# leo_FLOORSEN.net
KiCad netlist of a schematic drawn in Altium Designer
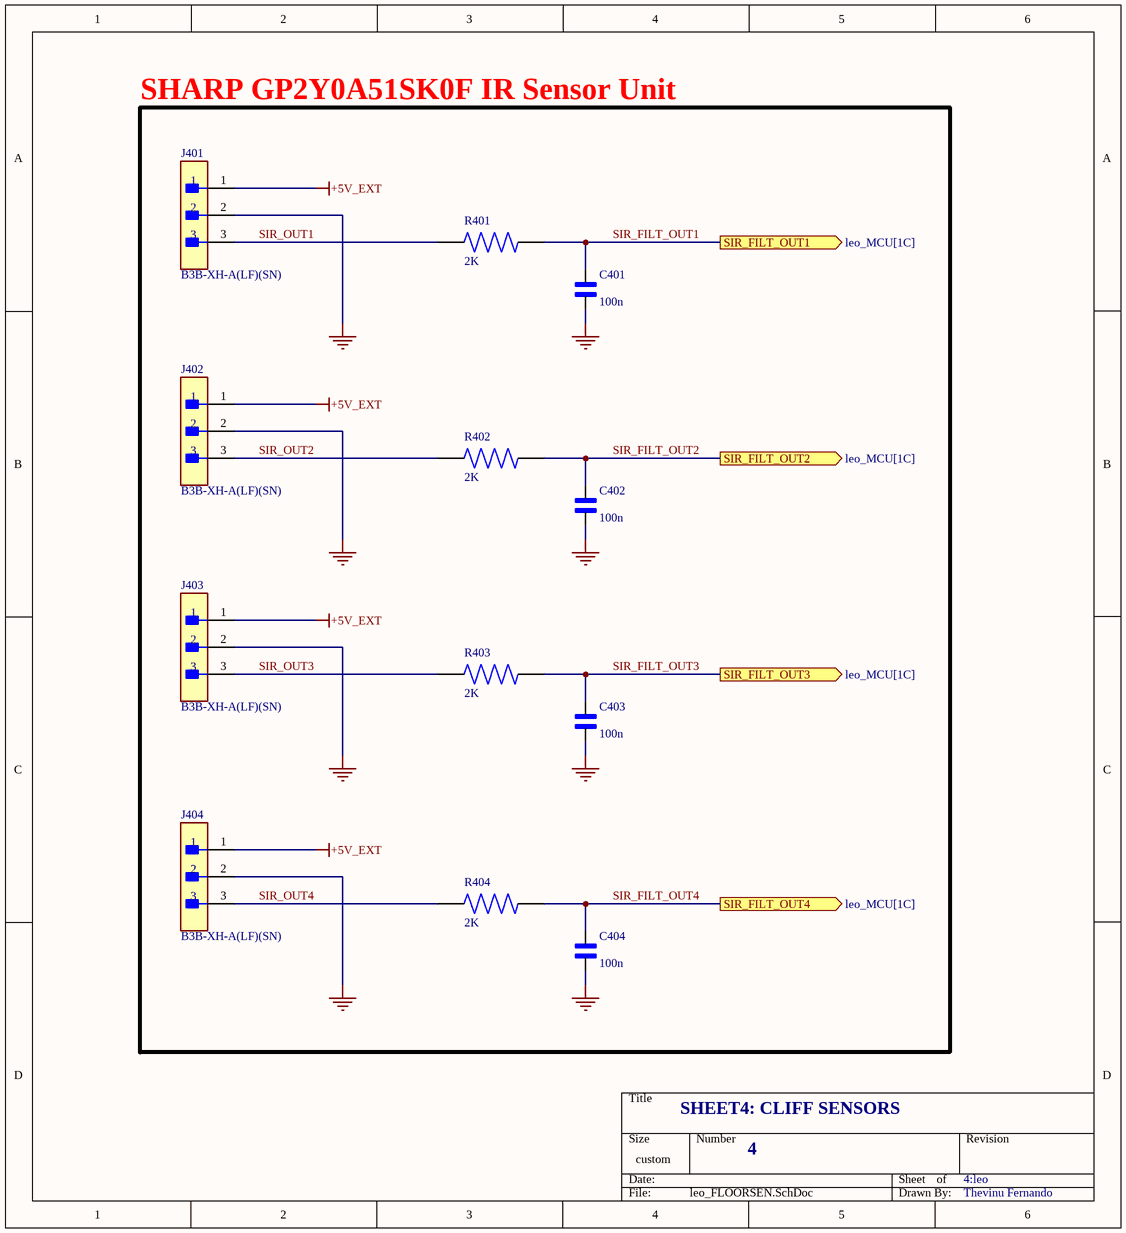
[diagram p0: leo_FLOORSEN.SchDoc]

(export (version "E")
  (design (tool "Eeschema 10.0.6"))
  (components
    (comp (ref "C401")
      (value "100n")
      (footprint "CAP_0402")
      (description "Ceramic Capacitor X7R 0402 (1005 Metric)")
      (fields (field (name "MF") "Samsung") (field (name "MP") "CL05B104KO5NNNC"))
      (libsource (lib "leo_schlib") (part "CAP_0402"))
    )
    (comp (ref "C402")
      (value "100n")
      (footprint "CAP_0402")
      (description "Ceramic Capacitor X7R 0402 (1005 Metric)")
      (fields (field (name "MF") "Samsung") (field (name "MP") "CL05B104KO5NNNC"))
      (libsource (lib "leo_schlib") (part "CAP_0402"))
    )
    (comp (ref "C403")
      (value "100n")
      (footprint "CAP_0402")
      (description "Ceramic Capacitor X7R 0402 (1005 Metric)")
      (fields (field (name "MF") "Samsung") (field (name "MP") "CL05B104KO5NNNC"))
      (libsource (lib "leo_schlib") (part "CAP_0402"))
    )
    (comp (ref "C404")
      (value "100n")
      (footprint "CAP_0402")
      (description "Ceramic Capacitor X7R 0402 (1005 Metric)")
      (fields (field (name "MF") "Samsung") (field (name "MP") "CL05B104KO5NNNC"))
      (libsource (lib "leo_schlib") (part "CAP_0402"))
    )
    (comp (ref "J401")
      (value "B3B-XH-A(LF)(SN)")
      (footprint "FP-B3B-XH-A_LF_SN-MFG")
      (description "CONN HEADER VERT 3POS 2.5MM")
      (libsource (lib "leo_schlib") (part "B3B-XH-A(LF)(SN)"))
    )
    (comp (ref "J402")
      (value "B3B-XH-A(LF)(SN)")
      (footprint "FP-B3B-XH-A_LF_SN-MFG")
      (description "CONN HEADER VERT 3POS 2.5MM")
      (libsource (lib "leo_schlib") (part "B3B-XH-A(LF)(SN)"))
    )
    (comp (ref "J403")
      (value "B3B-XH-A(LF)(SN)")
      (footprint "FP-B3B-XH-A_LF_SN-MFG")
      (description "CONN HEADER VERT 3POS 2.5MM")
      (libsource (lib "leo_schlib") (part "B3B-XH-A(LF)(SN)"))
    )
    (comp (ref "J404")
      (value "B3B-XH-A(LF)(SN)")
      (footprint "FP-B3B-XH-A_LF_SN-MFG")
      (description "CONN HEADER VERT 3POS 2.5MM")
      (libsource (lib "leo_schlib") (part "B3B-XH-A(LF)(SN)"))
    )
    (comp (ref "R401")
      (value "2K")
      (footprint "RES_0402")
      (description "Chip Resistor 0402 (1005 Metric) Automotive AEC-Q200 Thick Film")
      (fields (field (name "MF") "Panasonic") (field (name "MP") "ERJ-2RKF1002X"))
      (libsource (lib "leo_schlib") (part "RES_0402"))
    )
    (comp (ref "R402")
      (value "2K")
      (footprint "RES_0402")
      (description "Chip Resistor 0402 (1005 Metric) Automotive AEC-Q200 Thick Film")
      (fields (field (name "MF") "Panasonic") (field (name "MP") "ERJ-2RKF1002X"))
      (libsource (lib "leo_schlib") (part "RES_0402"))
    )
    (comp (ref "R403")
      (value "2K")
      (footprint "RES_0402")
      (description "Chip Resistor 0402 (1005 Metric) Automotive AEC-Q200 Thick Film")
      (fields (field (name "MF") "Panasonic") (field (name "MP") "ERJ-2RKF1002X"))
      (libsource (lib "leo_schlib") (part "RES_0402"))
    )
    (comp (ref "R404")
      (value "2K")
      (footprint "RES_0402")
      (description "Chip Resistor 0402 (1005 Metric) Automotive AEC-Q200 Thick Film")
      (fields (field (name "MF") "Panasonic") (field (name "MP") "ERJ-2RKF1002X"))
      (libsource (lib "leo_schlib") (part "RES_0402"))
    )
  )
  (nets
    (net (code "1") (name "+5V_EXT") (class "Default")
      (node (ref "J401") (pin "1") (pinfunction "1_1") (pintype "passive"))
      (node (ref "J402") (pin "1") (pinfunction "1_1") (pintype "passive"))
      (node (ref "J403") (pin "1") (pinfunction "1_1") (pintype "passive"))
      (node (ref "J404") (pin "1") (pinfunction "1_1") (pintype "passive"))
    )
    (net (code "2") (name "/SIR_FILT_OUT1") (class "Default")
      (node (ref "C401") (pin "2") (pinfunction "2_2") (pintype "passive"))
      (node (ref "R401") (pin "2") (pinfunction "2_2") (pintype "passive"))
    )
    (net (code "3") (name "/SIR_FILT_OUT2") (class "Default")
      (node (ref "C402") (pin "2") (pinfunction "2_2") (pintype "passive"))
      (node (ref "R402") (pin "2") (pinfunction "2_2") (pintype "passive"))
    )
    (net (code "4") (name "/SIR_FILT_OUT3") (class "Default")
      (node (ref "C403") (pin "2") (pinfunction "2_2") (pintype "passive"))
      (node (ref "R403") (pin "2") (pinfunction "2_2") (pintype "passive"))
    )
    (net (code "5") (name "/SIR_FILT_OUT4") (class "Default")
      (node (ref "C404") (pin "2") (pinfunction "2_2") (pintype "passive"))
      (node (ref "R404") (pin "2") (pinfunction "2_2") (pintype "passive"))
    )
    (net (code "6") (name "/SIR_OUT1") (class "Default")
      (node (ref "J401") (pin "3") (pinfunction "3_3") (pintype "passive"))
      (node (ref "R401") (pin "1") (pinfunction "1_1") (pintype "passive"))
    )
    (net (code "7") (name "/SIR_OUT2") (class "Default")
      (node (ref "J402") (pin "3") (pinfunction "3_3") (pintype "passive"))
      (node (ref "R402") (pin "1") (pinfunction "1_1") (pintype "passive"))
    )
    (net (code "8") (name "/SIR_OUT3") (class "Default")
      (node (ref "J403") (pin "3") (pinfunction "3_3") (pintype "passive"))
      (node (ref "R403") (pin "1") (pinfunction "1_1") (pintype "passive"))
    )
    (net (code "9") (name "/SIR_OUT4") (class "Default")
      (node (ref "J404") (pin "3") (pinfunction "3_3") (pintype "passive"))
      (node (ref "R404") (pin "1") (pinfunction "1_1") (pintype "passive"))
    )
    (net (code "10") (name "GND") (class "Default")
      (node (ref "C401") (pin "1") (pinfunction "1_1") (pintype "passive"))
      (node (ref "C402") (pin "1") (pinfunction "1_1") (pintype "passive"))
      (node (ref "C403") (pin "1") (pinfunction "1_1") (pintype "passive"))
      (node (ref "C404") (pin "1") (pinfunction "1_1") (pintype "passive"))
      (node (ref "J401") (pin "2") (pinfunction "2_2") (pintype "passive"))
      (node (ref "J402") (pin "2") (pinfunction "2_2") (pintype "passive"))
      (node (ref "J403") (pin "2") (pinfunction "2_2") (pintype "passive"))
      (node (ref "J404") (pin "2") (pinfunction "2_2") (pintype "passive"))
    )
  )
)
